# A4a_Wireless_Stick_Lite.net
KiCad netlist of a schematic drawn in EAGLE
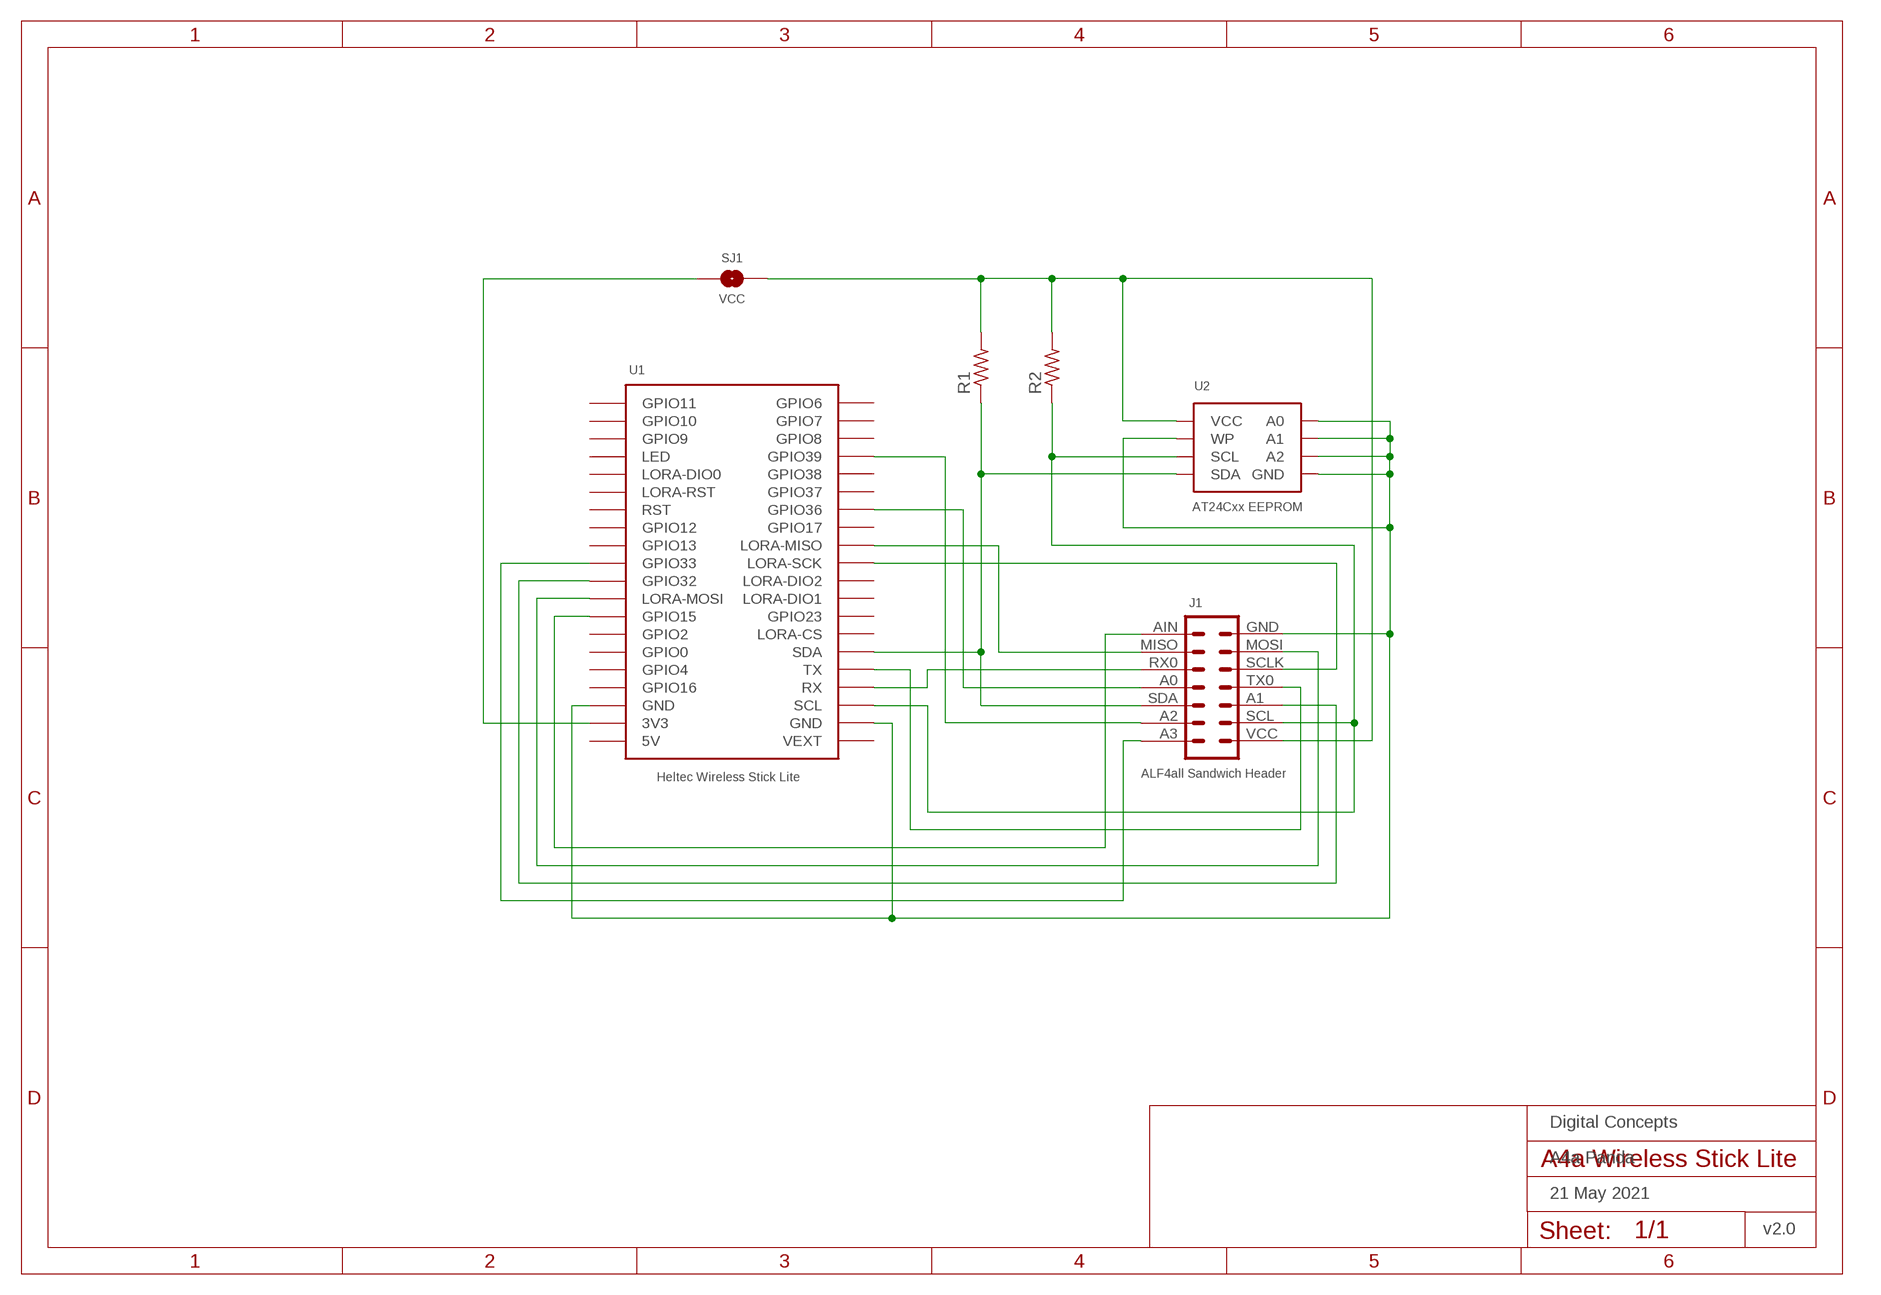
[diagram p0: schematic, sheet 1]

(export (version "E")
  (design (tool "Eeschema 10.0.6"))
  (components
    (comp (ref "J1")
      (value "ALF4all Sandwich Header")
      (footprint "eagle-import:CONN_2X7-ALF4ALL-PROCESSOR-B")
      (libsource (lib "eagle-import") (part "HEADER-2X7-ALF4ALL-PROCESSOR-B"))
    )
    (comp (ref "R1")
      (value "RESISTOR-VIA-1")
      (footprint "eagle-import:R0805-VIA-1")
      (libsource (lib "eagle-import") (part "RESISTOR-VIA-1"))
    )
    (comp (ref "R2")
      (value "RESISTOR-VIA-1")
      (footprint "eagle-import:R0805-VIA-1")
      (libsource (lib "eagle-import") (part "RESISTOR-VIA-1"))
    )
    (comp (ref "SJ1")
      (value "VCC")
      (footprint "eagle-import:SJ")
      (libsource (lib "eagle-import") (part "SJ"))
    )
    (comp (ref "U1")
      (value "Heltec Wireless Stick Lite")
      (footprint "eagle-import:HELTEC-WIRELESS-STICK-LITE")
      (libsource (lib "eagle-import") (part "HELTEC-WIRELESS-STICK-LITE"))
    )
    (comp (ref "U2")
      (value "AT24Cxx EEPROM")
      (footprint "eagle-import:SOP-8-WITH-VIA-7")
      (libsource (lib "eagle-import") (part "AT24CXX-EEPROM-VIA-7"))
    )
  )
  (nets
    (net (code "1") (name "Net-(J1-1)") (class "Default")
      (node (ref "J1") (pin "VCC") (pinfunction "1_VCC") (pintype "passive"))
      (node (ref "R1") (pin "2") (pinfunction "2_2") (pintype "passive"))
      (node (ref "R2") (pin "2") (pinfunction "2_2") (pintype "passive"))
      (node (ref "SJ1") (pin "2") (pinfunction "2_2") (pintype "passive"))
      (node (ref "U2") (pin "P$8") (pinfunction "VCC_P$8") (pintype "bidirectional"))
    )
    (net (code "2") (name "Net-(J1-2)") (class "Default")
      (node (ref "J1") (pin "SCL") (pinfunction "2_SCL") (pintype "passive"))
      (node (ref "R2") (pin "1") (pinfunction "1_1") (pintype "passive"))
      (node (ref "R2") (pin "1@VIA") (pinfunction "1_1@VIA") (pintype "passive"))
      (node (ref "U1") (pin "SCL") (pinfunction "SCL_SCL") (pintype "bidirectional"))
      (node (ref "U2") (pin "P$6") (pinfunction "SCL_P$6") (pintype "bidirectional"))
    )
    (net (code "3") (name "Net-(J1-3)") (class "Default")
      (node (ref "J1") (pin "A1") (pinfunction "3_A1") (pintype "passive"))
      (node (ref "U1") (pin "GPIO32") (pinfunction "GPIO32_GPIO32") (pintype "bidirectional"))
    )
    (net (code "4") (name "Net-(J1-4)") (class "Default")
      (node (ref "J1") (pin "TX0") (pinfunction "4_TX0") (pintype "passive"))
      (node (ref "U1") (pin "TX") (pinfunction "TX_TX") (pintype "bidirectional"))
    )
    (net (code "5") (name "Net-(J1-5)") (class "Default")
      (node (ref "J1") (pin "SCLK") (pinfunction "5_SCLK") (pintype "passive"))
      (node (ref "U1") (pin "LORA-SCK") (pinfunction "LORA-SCK_LORA-SCK") (pintype "bidirectional"))
    )
    (net (code "6") (name "Net-(J1-6)") (class "Default")
      (node (ref "J1") (pin "MOSI") (pinfunction "6_MOSI") (pintype "passive"))
      (node (ref "U1") (pin "LORA-MOSI") (pinfunction "LORA-MOSI_LORA-MOSI") (pintype "bidirectional"))
    )
    (net (code "7") (name "Net-(J1-7)") (class "Default")
      (node (ref "J1") (pin "GND") (pinfunction "7_GND") (pintype "passive"))
      (node (ref "U1") (pin "GND@18") (pinfunction "GND_GND@18") (pintype "bidirectional"))
      (node (ref "U1") (pin "GND@22") (pinfunction "GND_GND@22") (pintype "bidirectional"))
      (node (ref "U2") (pin "P$1") (pinfunction "A0_P$1") (pintype "bidirectional"))
      (node (ref "U2") (pin "P$2") (pinfunction "A1_P$2") (pintype "bidirectional"))
      (node (ref "U2") (pin "P$3") (pinfunction "A2_P$3") (pintype "bidirectional"))
      (node (ref "U2") (pin "P$4") (pinfunction "GND_P$4") (pintype "bidirectional"))
      (node (ref "U2") (pin "P$7") (pinfunction "WP_P$7") (pintype "bidirectional"))
      (node (ref "U2") (pin "P$7@VIA") (pinfunction "WP_P$7@VIA") (pintype "bidirectional"))
    )
    (net (code "8") (name "Net-(J1-8)") (class "Default")
      (node (ref "J1") (pin "AIN") (pinfunction "8_AIN") (pintype "passive"))
      (node (ref "U1") (pin "GPIO15") (pinfunction "GPIO15_GPIO15") (pintype "bidirectional"))
    )
    (net (code "9") (name "Net-(J1-9)") (class "Default")
      (node (ref "J1") (pin "MISO") (pinfunction "9_MISO") (pintype "passive"))
      (node (ref "U1") (pin "LORA-MISO") (pinfunction "LORA-MISO_LORA-MISO") (pintype "bidirectional"))
    )
    (net (code "10") (name "Net-(J1-10)") (class "Default")
      (node (ref "J1") (pin "RX0") (pinfunction "10_RX0") (pintype "passive"))
      (node (ref "U1") (pin "RX") (pinfunction "RX_RX") (pintype "bidirectional"))
    )
    (net (code "11") (name "Net-(J1-11)") (class "Default")
      (node (ref "J1") (pin "A0") (pinfunction "11_A0") (pintype "passive"))
      (node (ref "U1") (pin "GPIO36") (pinfunction "GPIO36_GPIO36") (pintype "bidirectional"))
    )
    (net (code "12") (name "Net-(J1-12)") (class "Default")
      (node (ref "J1") (pin "SDA") (pinfunction "12_SDA") (pintype "passive"))
      (node (ref "R1") (pin "1") (pinfunction "1_1") (pintype "passive"))
      (node (ref "R1") (pin "1@VIA") (pinfunction "1_1@VIA") (pintype "passive"))
      (node (ref "U1") (pin "SDA") (pinfunction "SDA_SDA") (pintype "bidirectional"))
      (node (ref "U2") (pin "P$5") (pinfunction "SDA_P$5") (pintype "bidirectional"))
    )
    (net (code "13") (name "Net-(J1-13)") (class "Default")
      (node (ref "J1") (pin "A2") (pinfunction "13_A2") (pintype "passive"))
      (node (ref "U1") (pin "GPIO39") (pinfunction "GPIO39_GPIO39") (pintype "bidirectional"))
    )
    (net (code "14") (name "Net-(J1-14)") (class "Default")
      (node (ref "J1") (pin "A3") (pinfunction "14_A3") (pintype "passive"))
      (node (ref "U1") (pin "GPIO33") (pinfunction "GPIO33_GPIO33") (pintype "bidirectional"))
    )
    (net (code "15") (name "Net-(SJ1-Pad1)") (class "Default")
      (node (ref "SJ1") (pin "1") (pinfunction "1_1") (pintype "passive"))
      (node (ref "U1") (pin "3V3") (pinfunction "3V3_3V3") (pintype "bidirectional"))
    )
    (net (code "16") (name "unconnected-(U1-Pad5V)") (class "Default")
      (node (ref "U1") (pin "5V") (pinfunction "5V_5V") (pintype "bidirectional"))
    )
    (net (code "17") (name "unconnected-(U1-PadGPIO0)") (class "Default")
      (node (ref "U1") (pin "GPIO0") (pinfunction "GPIO0_GPIO0") (pintype "bidirectional"))
    )
    (net (code "18") (name "unconnected-(U1-PadGPIO2)") (class "Default")
      (node (ref "U1") (pin "GPIO2") (pinfunction "GPIO2_GPIO2") (pintype "bidirectional"))
    )
    (net (code "19") (name "unconnected-(U1-PadGPIO4)") (class "Default")
      (node (ref "U1") (pin "GPIO4") (pinfunction "GPIO4_GPIO4") (pintype "bidirectional"))
    )
    (net (code "20") (name "unconnected-(U1-PadGPIO6)") (class "Default")
      (node (ref "U1") (pin "GPIO6") (pinfunction "GPIO6_GPIO6") (pintype "bidirectional"))
    )
    (net (code "21") (name "unconnected-(U1-PadGPIO7)") (class "Default")
      (node (ref "U1") (pin "GPIO7") (pinfunction "GPIO7_GPIO7") (pintype "bidirectional"))
    )
    (net (code "22") (name "unconnected-(U1-PadGPIO8)") (class "Default")
      (node (ref "U1") (pin "GPIO8") (pinfunction "GPIO8_GPIO8") (pintype "bidirectional"))
    )
    (net (code "23") (name "unconnected-(U1-PadGPIO9)") (class "Default")
      (node (ref "U1") (pin "GPIO9") (pinfunction "GPIO9_GPIO9") (pintype "bidirectional"))
    )
    (net (code "24") (name "unconnected-(U1-PadGPIO10)") (class "Default")
      (node (ref "U1") (pin "GPIO10") (pinfunction "GPIO10_GPIO10") (pintype "bidirectional"))
    )
    (net (code "25") (name "unconnected-(U1-PadGPIO11)") (class "Default")
      (node (ref "U1") (pin "GPIO11") (pinfunction "GPIO11_GPIO11") (pintype "bidirectional"))
    )
    (net (code "26") (name "unconnected-(U1-PadGPIO12)") (class "Default")
      (node (ref "U1") (pin "GPIO12") (pinfunction "GPIO12_GPIO12") (pintype "bidirectional"))
    )
    (net (code "27") (name "unconnected-(U1-PadGPIO13)") (class "Default")
      (node (ref "U1") (pin "GPIO13") (pinfunction "GPIO13_GPIO13") (pintype "bidirectional"))
    )
    (net (code "28") (name "unconnected-(U1-PadGPIO16)") (class "Default")
      (node (ref "U1") (pin "GPIO16") (pinfunction "GPIO16_GPIO16") (pintype "bidirectional"))
    )
    (net (code "29") (name "unconnected-(U1-PadGPIO17)") (class "Default")
      (node (ref "U1") (pin "GPIO17") (pinfunction "GPIO17_GPIO17") (pintype "bidirectional"))
    )
    (net (code "30") (name "unconnected-(U1-PadGPIO23)") (class "Default")
      (node (ref "U1") (pin "GPIO23") (pinfunction "GPIO23_GPIO23") (pintype "bidirectional"))
    )
    (net (code "31") (name "unconnected-(U1-PadGPIO37)") (class "Default")
      (node (ref "U1") (pin "GPIO37") (pinfunction "GPIO37_GPIO37") (pintype "bidirectional"))
    )
    (net (code "32") (name "unconnected-(U1-PadGPIO38)") (class "Default")
      (node (ref "U1") (pin "GPIO38") (pinfunction "GPIO38_GPIO38") (pintype "bidirectional"))
    )
    (net (code "33") (name "unconnected-(U1-PadLED)") (class "Default")
      (node (ref "U1") (pin "LED") (pinfunction "LED_LED") (pintype "bidirectional"))
    )
    (net (code "34") (name "unconnected-(U1-PadLORA-CS)") (class "Default")
      (node (ref "U1") (pin "LORA-CS") (pinfunction "LORA-CS_LORA-CS") (pintype "bidirectional"))
    )
    (net (code "35") (name "unconnected-(U1-PadLORA-DIO0)") (class "Default")
      (node (ref "U1") (pin "LORA-DIO0") (pinfunction "LORA-DIO0_LORA-DIO0") (pintype "bidirectional"))
    )
    (net (code "36") (name "unconnected-(U1-PadLORA-DIO1)") (class "Default")
      (node (ref "U1") (pin "LORA-DIO1") (pinfunction "LORA-DIO1_LORA-DIO1") (pintype "bidirectional"))
    )
    (net (code "37") (name "unconnected-(U1-PadLORA-DIO2)") (class "Default")
      (node (ref "U1") (pin "LORA-DIO2") (pinfunction "LORA-DIO2_LORA-DIO2") (pintype "bidirectional"))
    )
    (net (code "38") (name "unconnected-(U1-PadLORA-RST)") (class "Default")
      (node (ref "U1") (pin "LORA-RST") (pinfunction "LORA-RST_LORA-RST") (pintype "bidirectional"))
    )
    (net (code "39") (name "unconnected-(U1-PadRST)") (class "Default")
      (node (ref "U1") (pin "RST") (pinfunction "RST_RST") (pintype "bidirectional"))
    )
    (net (code "40") (name "unconnected-(U1-PadVEXT)") (class "Default")
      (node (ref "U1") (pin "VEXT") (pinfunction "VEXT_VEXT") (pintype "bidirectional"))
    )
  )
)
